# Modbus.net
KiCad netlist of a schematic drawn in Altium Designer
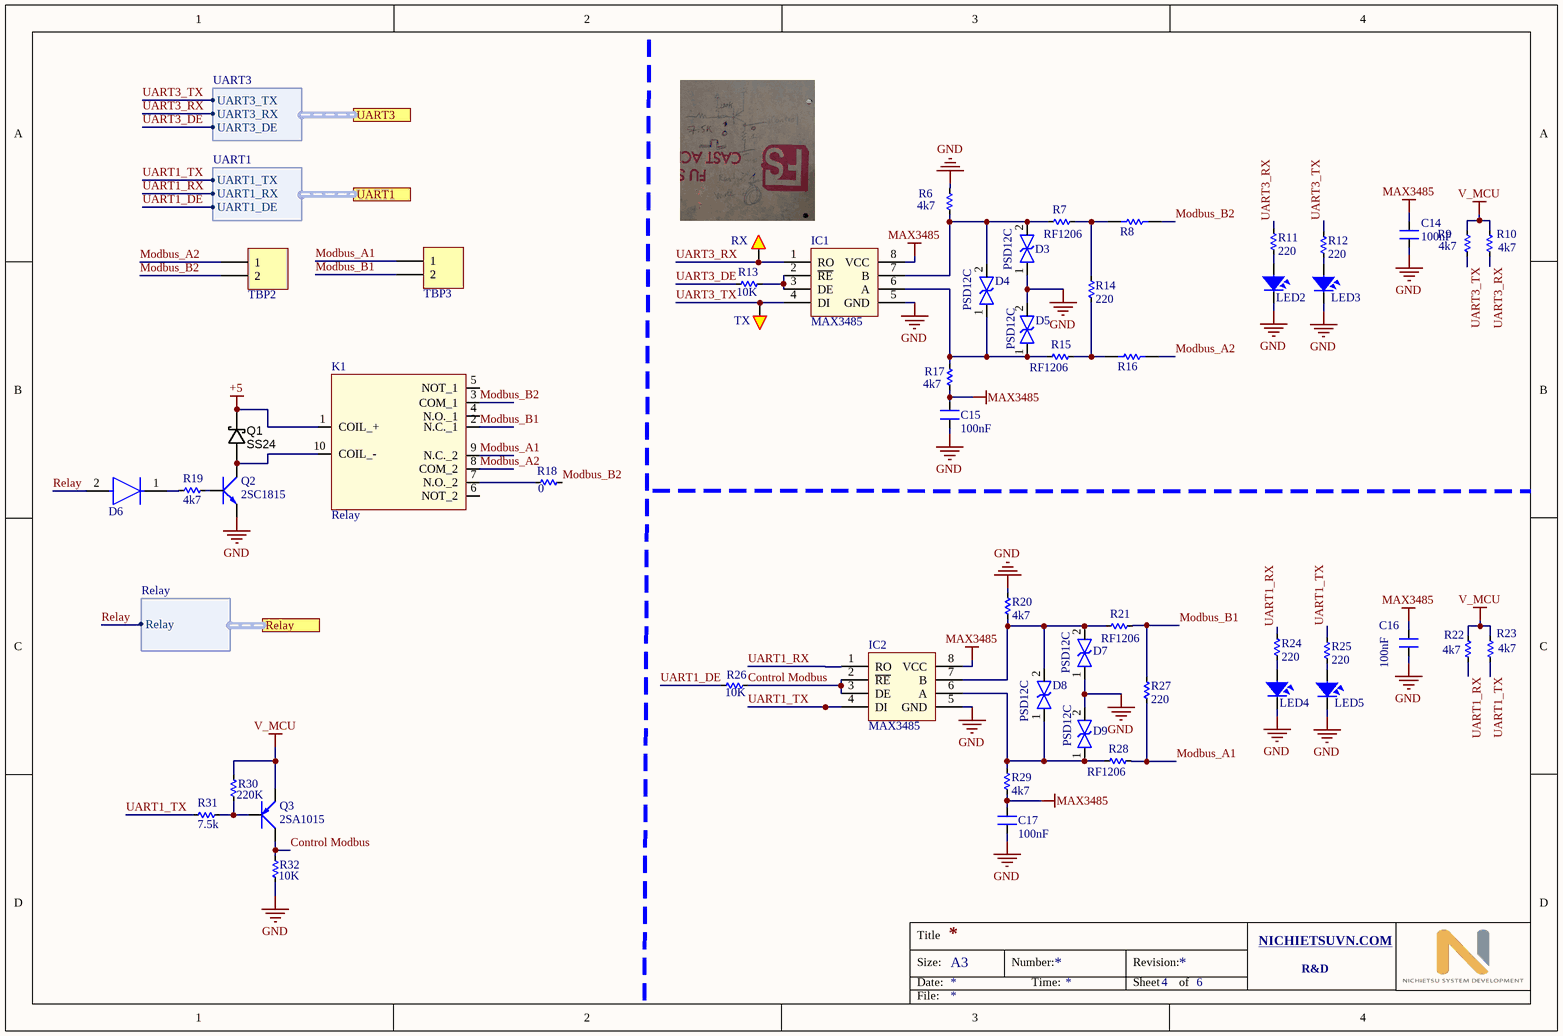
[diagram p0: Modbus.SchDoc]

(export (version "E")
  (design (tool "Eeschema 10.0.6"))
  (components
    (comp (ref "B1")
      (value "RX")
      (footprint "SMD_1.5")
      (description "WR-PHD 2.54 mm Angled Socket Header")
      (fields
        (field (name "MANUFACTURER") "Würth Elektronik eiSos GmbH")
        (field (name "PARTNO") "613002143121")
        (field (name "CREATED BY") "Karrer Zheng")
      )
      (libsource (lib "Nichietsuvn") (part "Test"))
    )
    (comp (ref "B2")
      (value "TX")
      (footprint "SMD_1.5")
      (description "WR-PHD 2.54 mm Angled Socket Header")
      (fields
        (field (name "MANUFACTURER") "Würth Elektronik eiSos GmbH")
        (field (name "PARTNO") "613002143121")
        (field (name "CREATED BY") "Karrer Zheng")
      )
      (libsource (lib "Nichietsuvn") (part "Test"))
    )
    (comp (ref "C14") (value "100nF") (footprint "CN-SMD-0603") (libsource (lib "thu vien 3d") (part "CN")))
    (comp (ref "C15") (value "100nF") (footprint "CN-SMD-0603") (libsource (lib "thu vien 3d") (part "CN")))
    (comp (ref "C16") (value "100nF") (footprint "CN-SMD-0603") (libsource (lib "thu vien 3d") (part "CN")))
    (comp (ref "C17") (value "100nF") (footprint "CN-SMD-0603") (libsource (lib "thu vien 3d") (part "CN")))
    (comp (ref "D3")
      (value "PSD12C")
      (footprint "PSD12C")
      (description "diode tvs")
      (libsource (lib "Nichietsuvn") (part "PSD12C"))
    )
    (comp (ref "D4")
      (value "PSD12C")
      (footprint "PSD12C")
      (description "diode tvs")
      (libsource (lib "Nichietsuvn") (part "PSD12C"))
    )
    (comp (ref "D5")
      (value "PSD12C")
      (footprint "PSD12C")
      (description "diode tvs")
      (libsource (lib "Nichietsuvn") (part "PSD12C"))
    )
    (comp (ref "D6")
      (value "1N4148W-HE3-08")
      (footprint "1N4148")
      (libsource (lib "All Library") (part "1N4148W-HE3-08"))
    )
    (comp (ref "D7")
      (value "PSD12C")
      (footprint "PSD12C")
      (description "diode tvs")
      (libsource (lib "Nichietsuvn") (part "PSD12C"))
    )
    (comp (ref "D8")
      (value "PSD12C")
      (footprint "PSD12C")
      (description "diode tvs")
      (libsource (lib "Nichietsuvn") (part "PSD12C"))
    )
    (comp (ref "D9")
      (value "PSD12C")
      (footprint "PSD12C")
      (description "diode tvs")
      (libsource (lib "Nichietsuvn") (part "PSD12C"))
    )
    (comp (ref "IC1")
      (value "MAX3485")
      (footprint "SO8")
      (description "RS232 - RS485 (Same sn75176)")
      (libsource (lib "thu vien 3d") (part "MAX485"))
    )
    (comp (ref "IC2")
      (value "MAX3485")
      (footprint "SO8")
      (description "RS232 - RS485 (Same sn75176)")
      (libsource (lib "thu vien 3d") (part "MAX485"))
    )
    (comp (ref "K1")
      (value "Relay")
      (footprint "Relay EA2")
      (description "Relay or Contactor")
      (fields (field (name "MANUFACTURER_PART_NUMBER") "EA2-5NU"))
      (libsource (lib "All Library") (part "EA2-5NU"))
    )
    (comp (ref "LED2")
      (value "LED")
      (footprint "LED-0805-Blue")
      (libsource (lib "thu vien 3d") (part "LED SMD"))
    )
    (comp (ref "LED3")
      (value "LED")
      (footprint "LED-0805-Blue")
      (libsource (lib "thu vien 3d") (part "LED SMD"))
    )
    (comp (ref "LED4")
      (value "LED")
      (footprint "LED-0805-Blue")
      (libsource (lib "thu vien 3d") (part "LED SMD"))
    )
    (comp (ref "LED5")
      (value "LED")
      (footprint "LED-0805-Blue")
      (libsource (lib "thu vien 3d") (part "LED SMD"))
    )
    (comp (ref "Q1")
      (value "SS24")
      (footprint "DO-214AC")
      (description "Diode Schottky 40V 2A Surface Mount DO-214AC (SMA)")
      (libsource (lib "All Library") (part "DIODE_SS24"))
    )
    (comp (ref "Q2")
      (value "2SC1815")
      (footprint "SOT23-321")
      (description "NPN 600mW, ECB")
      (libsource (lib "thu vien 3d") (part "2SC1815"))
    )
    (comp (ref "Q3")
      (value "2SA1015")
      (footprint "SOT23-321")
      (description "PNP 600mW, ECB")
      (libsource (lib "thu vien 3d") (part "2SA1015"))
    )
    (comp (ref "R6")
      (value "4k7")
      (footprint "RES-SMD-0603")
      (description "Resistor")
      (fields
        (field (name "MANUFACTURER") "Generic Components")
        (field (name "PUBLISHER") "Altium Hobart Technology Centre")
      )
      (libsource (lib "thu vien 3d") (part "Res-SMD"))
    )
    (comp (ref "R7")
      (value "RF1206")
      (footprint "RES-SMD-1206")
      (description "Resistor")
      (fields
        (field (name "MANUFACTURER") "Generic Components")
        (field (name "PUBLISHER") "Altium Hobart Technology Centre")
      )
      (libsource (lib "thu vien 3d") (part "Res-SMD"))
    )
    (comp (ref "R8")
      (value "0R/R0603")
      (footprint "R0603")
      (description "RES SMD 0.0OHM JUMPER 1/10W 0603")
      (fields
        (field (name "MANUFACTURER") "Yageo")
        (field (name "MANUFACTURER PART NUMBER") "RC0603JR-070RL")
      )
      (libsource (lib "All Library") (part "RES_0R_R0603"))
    )
    (comp (ref "R9")
      (value "4k7")
      (footprint "RES-SMD-0603")
      (description "Resistor")
      (fields
        (field (name "MANUFACTURER") "Generic Components")
        (field (name "PUBLISHER") "Altium Hobart Technology Centre")
      )
      (libsource (lib "thu vien 3d") (part "Res-SMD"))
    )
    (comp (ref "R10")
      (value "4k7")
      (footprint "RES-SMD-0603")
      (description "Resistor")
      (fields
        (field (name "MANUFACTURER") "Generic Components")
        (field (name "PUBLISHER") "Altium Hobart Technology Centre")
      )
      (libsource (lib "thu vien 3d") (part "Res-SMD"))
    )
    (comp (ref "R11")
      (value "220")
      (footprint "RES-SMD-0603")
      (description "Resistor")
      (fields
        (field (name "MANUFACTURER") "Generic Components")
        (field (name "PUBLISHER") "Altium Hobart Technology Centre")
      )
      (libsource (lib "thu vien 3d") (part "Res-SMD"))
    )
    (comp (ref "R12")
      (value "220")
      (footprint "RES-SMD-0603")
      (description "Resistor")
      (fields
        (field (name "MANUFACTURER") "Generic Components")
        (field (name "PUBLISHER") "Altium Hobart Technology Centre")
      )
      (libsource (lib "thu vien 3d") (part "Res-SMD"))
    )
    (comp (ref "R13")
      (value "10K")
      (footprint "RES-SMD-0603")
      (description "Resistor")
      (fields
        (field (name "MANUFACTURER") "Generic Components")
        (field (name "PUBLISHER") "Altium Hobart Technology Centre")
      )
      (libsource (lib "thu vien 3d") (part "Res-SMD"))
    )
    (comp (ref "R14")
      (value "220")
      (footprint "RES-SMD-0603")
      (description "Resistor")
      (fields
        (field (name "MANUFACTURER") "Generic Components")
        (field (name "PUBLISHER") "Altium Hobart Technology Centre")
      )
      (libsource (lib "thu vien 3d") (part "Res-SMD"))
    )
    (comp (ref "R15")
      (value "RF1206")
      (footprint "RES-SMD-1206")
      (description "Resistor")
      (fields
        (field (name "MANUFACTURER") "Generic Components")
        (field (name "PUBLISHER") "Altium Hobart Technology Centre")
      )
      (libsource (lib "thu vien 3d") (part "Res-SMD"))
    )
    (comp (ref "R16")
      (value "0R/R0603")
      (footprint "R0603")
      (description "RES SMD 0.0OHM JUMPER 1/10W 0603")
      (fields
        (field (name "MANUFACTURER") "Yageo")
        (field (name "MANUFACTURER PART NUMBER") "RC0603JR-070RL")
      )
      (libsource (lib "All Library") (part "RES_0R_R0603"))
    )
    (comp (ref "R17")
      (value "4k7")
      (footprint "RES-SMD-0603")
      (description "Resistor")
      (fields
        (field (name "MANUFACTURER") "Generic Components")
        (field (name "PUBLISHER") "Altium Hobart Technology Centre")
      )
      (libsource (lib "thu vien 3d") (part "Res-SMD"))
    )
    (comp (ref "R18")
      (value "0")
      (footprint "RES-SMD-0603")
      (description "Resistor")
      (fields
        (field (name "MANUFACTURER") "Generic Components")
        (field (name "PUBLISHER") "Altium Hobart Technology Centre")
      )
      (libsource (lib "thu vien 3d") (part "Res-SMD"))
    )
    (comp (ref "R19")
      (value "4k7")
      (footprint "RES-SMD-0603")
      (description "Resistor")
      (fields
        (field (name "MANUFACTURER") "Generic Components")
        (field (name "PUBLISHER") "Altium Hobart Technology Centre")
      )
      (libsource (lib "thu vien 3d") (part "Res-SMD"))
    )
    (comp (ref "R20")
      (value "4k7")
      (footprint "RES-SMD-0603")
      (description "Resistor")
      (fields
        (field (name "MANUFACTURER") "Generic Components")
        (field (name "PUBLISHER") "Altium Hobart Technology Centre")
      )
      (libsource (lib "thu vien 3d") (part "Res-SMD"))
    )
    (comp (ref "R21")
      (value "RF1206")
      (footprint "RES-SMD-1206")
      (description "Resistor")
      (fields
        (field (name "MANUFACTURER") "Generic Components")
        (field (name "PUBLISHER") "Altium Hobart Technology Centre")
      )
      (libsource (lib "thu vien 3d") (part "Res-SMD"))
    )
    (comp (ref "R22")
      (value "4k7")
      (footprint "RES-SMD-0603")
      (description "Resistor")
      (fields
        (field (name "MANUFACTURER") "Generic Components")
        (field (name "PUBLISHER") "Altium Hobart Technology Centre")
      )
      (libsource (lib "thu vien 3d") (part "Res-SMD"))
    )
    (comp (ref "R23")
      (value "4k7")
      (footprint "RES-SMD-0603")
      (description "Resistor")
      (fields
        (field (name "MANUFACTURER") "Generic Components")
        (field (name "PUBLISHER") "Altium Hobart Technology Centre")
      )
      (libsource (lib "thu vien 3d") (part "Res-SMD"))
    )
    (comp (ref "R24")
      (value "220")
      (footprint "RES-SMD-0603")
      (description "Resistor")
      (fields
        (field (name "MANUFACTURER") "Generic Components")
        (field (name "PUBLISHER") "Altium Hobart Technology Centre")
      )
      (libsource (lib "thu vien 3d") (part "Res-SMD"))
    )
    (comp (ref "R25")
      (value "220")
      (footprint "RES-SMD-0603")
      (description "Resistor")
      (fields
        (field (name "MANUFACTURER") "Generic Components")
        (field (name "PUBLISHER") "Altium Hobart Technology Centre")
      )
      (libsource (lib "thu vien 3d") (part "Res-SMD"))
    )
    (comp (ref "R26")
      (value "10K")
      (footprint "RES-SMD-0603")
      (description "Resistor")
      (fields
        (field (name "MANUFACTURER") "Generic Components")
        (field (name "PUBLISHER") "Altium Hobart Technology Centre")
      )
      (libsource (lib "thu vien 3d") (part "Res-SMD"))
    )
    (comp (ref "R27")
      (value "220")
      (footprint "RES-SMD-0603")
      (description "Resistor")
      (fields
        (field (name "MANUFACTURER") "Generic Components")
        (field (name "PUBLISHER") "Altium Hobart Technology Centre")
      )
      (libsource (lib "thu vien 3d") (part "Res-SMD"))
    )
    (comp (ref "R28")
      (value "RF1206")
      (footprint "RES-SMD-1206")
      (description "Resistor")
      (fields
        (field (name "MANUFACTURER") "Generic Components")
        (field (name "PUBLISHER") "Altium Hobart Technology Centre")
      )
      (libsource (lib "thu vien 3d") (part "Res-SMD"))
    )
    (comp (ref "R29")
      (value "4k7")
      (footprint "RES-SMD-0603")
      (description "Resistor")
      (fields
        (field (name "MANUFACTURER") "Generic Components")
        (field (name "PUBLISHER") "Altium Hobart Technology Centre")
      )
      (libsource (lib "thu vien 3d") (part "Res-SMD"))
    )
    (comp (ref "R30")
      (value "220K")
      (footprint "RES-SMD-0603")
      (description "Resistor")
      (fields
        (field (name "MANUFACTURER") "Generic Components")
        (field (name "PUBLISHER") "Altium Hobart Technology Centre")
      )
      (libsource (lib "thu vien 3d") (part "Res-SMD"))
    )
    (comp (ref "R31")
      (value "7.5k")
      (footprint "RES-SMD-0603")
      (description "Resistor")
      (fields
        (field (name "MANUFACTURER") "Generic Components")
        (field (name "PUBLISHER") "Altium Hobart Technology Centre")
      )
      (libsource (lib "thu vien 3d") (part "Res-SMD"))
    )
    (comp (ref "R32")
      (value "10K")
      (footprint "RES-SMD-0603")
      (description "Resistor")
      (fields
        (field (name "MANUFACTURER") "Generic Components")
        (field (name "PUBLISHER") "Altium Hobart Technology Centre")
      )
      (libsource (lib "thu vien 3d") (part "Res-SMD"))
    )
    (comp (ref "TBP2")
      (value "WE-Terminal Blocks Plugable Type 691322310002")
      (footprint "Terminal_Blocks_Pluggable_Socket__Right_Angle__3.81_mm_Pitch__2_Position")
      (description "WR-TBL Terminal block - serie 322 - 3.81 mm")
      (libsource (lib "All Library") (part "Terminal_Blocks_Pluggable_Socket__Right_Angle__3.81_mm_Pitch__2_Position"))
    )
    (comp (ref "TBP3")
      (value "WE-Terminal Blocks Plugable Type 691322310002")
      (footprint "Terminal_Blocks_Pluggable_Socket__Right_Angle__3.81_mm_Pitch__2_Position")
      (description "WR-TBL Terminal block - serie 322 - 3.81 mm")
      (libsource (lib "All Library") (part "Terminal_Blocks_Pluggable_Socket__Right_Angle__3.81_mm_Pitch__2_Position"))
    )
  )
  (nets
    (net (code "3") (name "+5") (class "Default")
      (node (ref "K1") (pin "1") (pinfunction "COIL_+_1") (pintype "passive"))
      (node (ref "Q1") (pin "C") (pinfunction "C_C") (pintype "passive"))
    )
    (net (code "4") (name "/Control Modbus") (class "Default")
      (node (ref "IC2") (pin "2") (pinfunction "~{RE}_2") (pintype "passive"))
      (node (ref "IC2") (pin "3") (pinfunction "DE_3") (pintype "passive"))
      (node (ref "Q3") (pin "2") (pinfunction "C_2") (pintype "passive"))
      (node (ref "R26") (pin "2") (pinfunction "2_2") (pintype "passive"))
      (node (ref "R32") (pin "2") (pinfunction "2_2") (pintype "passive"))
    )
    (net (code "5") (name "/Modbus_A1") (class "Default")
      (node (ref "K1") (pin "9") (pinfunction "N.C._2_9") (pintype "passive"))
      (node (ref "R27") (pin "2") (pinfunction "2_2") (pintype "passive"))
      (node (ref "R28") (pin "1") (pinfunction "1_1") (pintype "passive"))
      (node (ref "TBP3") (pin "1") (pinfunction "1_1") (pintype "passive"))
    )
    (net (code "6") (name "/Modbus_A2") (class "Default")
      (node (ref "K1") (pin "8") (pinfunction "COM_2_8") (pintype "passive"))
      (node (ref "R16") (pin "2") (pinfunction "2_2") (pintype "passive"))
      (node (ref "TBP2") (pin "1") (pinfunction "1_1") (pintype "passive"))
    )
    (net (code "7") (name "/Modbus_B1") (class "Default")
      (node (ref "K1") (pin "2") (pinfunction "N.C._1_2") (pintype "passive"))
      (node (ref "R21") (pin "1") (pinfunction "1_1") (pintype "passive"))
      (node (ref "R27") (pin "1") (pinfunction "1_1") (pintype "passive"))
      (node (ref "TBP3") (pin "2") (pinfunction "2_2") (pintype "passive"))
    )
    (net (code "8") (name "/Modbus_B2") (class "Default")
      (node (ref "K1") (pin "3") (pinfunction "COM_1_3") (pintype "passive"))
      (node (ref "R18") (pin "2") (pinfunction "2_2") (pintype "passive"))
      (node (ref "R8") (pin "2") (pinfunction "2_2") (pintype "passive"))
      (node (ref "TBP2") (pin "2") (pinfunction "2_2") (pintype "passive"))
    )
    (net (code "9") (name "/Relay") (class "Default")
      (node (ref "D6") (pin "2") (pinfunction "A_2") (pintype "passive"))
    )
    (net (code "10") (name "/UART1_DE") (class "Default")
      (node (ref "R26") (pin "1") (pinfunction "1_1") (pintype "passive"))
    )
    (net (code "11") (name "/UART1_RX") (class "Default")
      (node (ref "IC2") (pin "1") (pinfunction "RO_1") (pintype "passive"))
      (node (ref "R22") (pin "2") (pinfunction "2_2") (pintype "passive"))
      (node (ref "R24") (pin "1") (pinfunction "1_1") (pintype "passive"))
    )
    (net (code "12") (name "/UART1_TX") (class "Default")
      (node (ref "IC2") (pin "4") (pinfunction "DI_4") (pintype "passive"))
      (node (ref "R23") (pin "2") (pinfunction "2_2") (pintype "passive"))
      (node (ref "R25") (pin "1") (pinfunction "1_1") (pintype "passive"))
      (node (ref "R31") (pin "1") (pinfunction "1_1") (pintype "passive"))
    )
    (net (code "13") (name "/UART3_DE") (class "Default")
      (node (ref "R13") (pin "1") (pinfunction "1_1") (pintype "passive"))
    )
    (net (code "14") (name "/UART3_RX") (class "Default")
      (node (ref "B1") (pin "1") (pinfunction "1_1") (pintype "passive"))
      (node (ref "IC1") (pin "1") (pinfunction "RO_1") (pintype "passive"))
      (node (ref "R10") (pin "2") (pinfunction "2_2") (pintype "passive"))
      (node (ref "R11") (pin "1") (pinfunction "1_1") (pintype "passive"))
    )
    (net (code "15") (name "/UART3_TX") (class "Default")
      (node (ref "B2") (pin "1") (pinfunction "1_1") (pintype "passive"))
      (node (ref "IC1") (pin "4") (pinfunction "DI_4") (pintype "passive"))
      (node (ref "R12") (pin "1") (pinfunction "1_1") (pintype "passive"))
      (node (ref "R9") (pin "2") (pinfunction "2_2") (pintype "passive"))
    )
    (net (code "19") (name "GND") (class "Default")
      (node (ref "C14") (pin "1") (pinfunction "1_1") (pintype "passive"))
      (node (ref "C15") (pin "2") (pinfunction "2_2") (pintype "passive"))
      (node (ref "C16") (pin "1") (pinfunction "1_1") (pintype "passive"))
      (node (ref "C17") (pin "2") (pinfunction "2_2") (pintype "passive"))
      (node (ref "D3") (pin "1") (pinfunction "1_1") (pintype "passive"))
      (node (ref "D5") (pin "2") (pinfunction "2_2") (pintype "passive"))
      (node (ref "D7") (pin "1") (pinfunction "1_1") (pintype "passive"))
      (node (ref "D9") (pin "2") (pinfunction "2_2") (pintype "passive"))
      (node (ref "IC1") (pin "5") (pinfunction "GND_5") (pintype "passive"))
      (node (ref "IC2") (pin "5") (pinfunction "GND_5") (pintype "passive"))
      (node (ref "LED2") (pin "2") (pinfunction "2_2") (pintype "passive"))
      (node (ref "LED3") (pin "2") (pinfunction "2_2") (pintype "passive"))
      (node (ref "LED4") (pin "2") (pinfunction "2_2") (pintype "passive"))
      (node (ref "LED5") (pin "2") (pinfunction "2_2") (pintype "passive"))
      (node (ref "Q2") (pin "1") (pinfunction "E_1") (pintype "passive"))
      (node (ref "R20") (pin "1") (pinfunction "1_1") (pintype "passive"))
      (node (ref "R32") (pin "1") (pinfunction "1_1") (pintype "passive"))
      (node (ref "R6") (pin "1") (pinfunction "1_1") (pintype "passive"))
    )
    (net (code "20") (name "MAX3485") (class "Default")
      (node (ref "C14") (pin "2") (pinfunction "2_2") (pintype "passive"))
      (node (ref "C15") (pin "1") (pinfunction "1_1") (pintype "passive"))
      (node (ref "C16") (pin "2") (pinfunction "2_2") (pintype "passive"))
      (node (ref "C17") (pin "1") (pinfunction "1_1") (pintype "passive"))
      (node (ref "IC1") (pin "8") (pinfunction "VCC_8") (pintype "passive"))
      (node (ref "IC2") (pin "8") (pinfunction "VCC_8") (pintype "passive"))
      (node (ref "R17") (pin "1") (pinfunction "1_1") (pintype "passive"))
      (node (ref "R29") (pin "1") (pinfunction "1_1") (pintype "passive"))
    )
    (net (code "21") (name "Net-(D6-C)") (class "Default")
      (node (ref "D6") (pin "1") (pinfunction "C_1") (pintype "passive"))
      (node (ref "R19") (pin "2") (pinfunction "2_2") (pintype "passive"))
    )
    (net (code "22") (name "Net-(IC1-A)") (class "Default")
      (node (ref "D4") (pin "1") (pinfunction "1_1") (pintype "passive"))
      (node (ref "D5") (pin "1") (pinfunction "1_1") (pintype "passive"))
      (node (ref "IC1") (pin "6") (pinfunction "A_6") (pintype "passive"))
      (node (ref "R15") (pin "2") (pinfunction "2_2") (pintype "passive"))
      (node (ref "R17") (pin "2") (pinfunction "2_2") (pintype "passive"))
    )
    (net (code "23") (name "Net-(IC1-B)") (class "Default")
      (node (ref "D3") (pin "2") (pinfunction "2_2") (pintype "passive"))
      (node (ref "D4") (pin "2") (pinfunction "2_2") (pintype "passive"))
      (node (ref "IC1") (pin "7") (pinfunction "B_7") (pintype "passive"))
      (node (ref "R6") (pin "2") (pinfunction "2_2") (pintype "passive"))
      (node (ref "R7") (pin "2") (pinfunction "2_2") (pintype "passive"))
    )
    (net (code "24") (name "Net-(IC1-DE)") (class "Default")
      (node (ref "IC1") (pin "2") (pinfunction "~{RE}_2") (pintype "passive"))
      (node (ref "IC1") (pin "3") (pinfunction "DE_3") (pintype "passive"))
      (node (ref "R13") (pin "2") (pinfunction "2_2") (pintype "passive"))
    )
    (net (code "25") (name "Net-(IC2-A)") (class "Default")
      (node (ref "D8") (pin "1") (pinfunction "1_1") (pintype "passive"))
      (node (ref "D9") (pin "1") (pinfunction "1_1") (pintype "passive"))
      (node (ref "IC2") (pin "6") (pinfunction "A_6") (pintype "passive"))
      (node (ref "R28") (pin "2") (pinfunction "2_2") (pintype "passive"))
      (node (ref "R29") (pin "2") (pinfunction "2_2") (pintype "passive"))
    )
    (net (code "26") (name "Net-(IC2-B)") (class "Default")
      (node (ref "D7") (pin "2") (pinfunction "2_2") (pintype "passive"))
      (node (ref "D8") (pin "2") (pinfunction "2_2") (pintype "passive"))
      (node (ref "IC2") (pin "7") (pinfunction "B_7") (pintype "passive"))
      (node (ref "R20") (pin "2") (pinfunction "2_2") (pintype "passive"))
      (node (ref "R21") (pin "2") (pinfunction "2_2") (pintype "passive"))
    )
    (net (code "27") (name "Net-(K1-COIL_-)") (class "Default")
      (node (ref "K1") (pin "10") (pinfunction "COIL_-_10") (pintype "passive"))
      (node (ref "Q1") (pin "A") (pinfunction "A_A") (pintype "passive"))
      (node (ref "Q2") (pin "2") (pinfunction "C_2") (pintype "passive"))
    )
    (net (code "28") (name "Net-(K1-N.O._2)") (class "Default")
      (node (ref "K1") (pin "7") (pinfunction "N.O._2_7") (pintype "passive"))
      (node (ref "R18") (pin "1") (pinfunction "1_1") (pintype "passive"))
    )
    (net (code "29") (name "Net-(LED2-Pad1)") (class "Default")
      (node (ref "LED2") (pin "1") (pinfunction "1_1") (pintype "passive"))
      (node (ref "R11") (pin "2") (pinfunction "2_2") (pintype "passive"))
    )
    (net (code "30") (name "Net-(LED3-Pad1)") (class "Default")
      (node (ref "LED3") (pin "1") (pinfunction "1_1") (pintype "passive"))
      (node (ref "R12") (pin "2") (pinfunction "2_2") (pintype "passive"))
    )
    (net (code "31") (name "Net-(LED4-Pad1)") (class "Default")
      (node (ref "LED4") (pin "1") (pinfunction "1_1") (pintype "passive"))
      (node (ref "R24") (pin "2") (pinfunction "2_2") (pintype "passive"))
    )
    (net (code "32") (name "Net-(LED5-Pad1)") (class "Default")
      (node (ref "LED5") (pin "1") (pinfunction "1_1") (pintype "passive"))
      (node (ref "R25") (pin "2") (pinfunction "2_2") (pintype "passive"))
    )
    (net (code "33") (name "Net-(Q2-B)") (class "Default")
      (node (ref "Q2") (pin "3") (pinfunction "B_3") (pintype "passive"))
      (node (ref "R19") (pin "1") (pinfunction "1_1") (pintype "passive"))
    )
    (net (code "34") (name "Net-(Q3-B)") (class "Default")
      (node (ref "Q3") (pin "3") (pinfunction "B_3") (pintype "passive"))
      (node (ref "R30") (pin "1") (pinfunction "1_1") (pintype "passive"))
      (node (ref "R31") (pin "2") (pinfunction "2_2") (pintype "passive"))
    )
    (net (code "35") (name "Net-(R14-Pad1)") (class "Default")
      (node (ref "R14") (pin "1") (pinfunction "1_1") (pintype "passive"))
      (node (ref "R7") (pin "1") (pinfunction "1_1") (pintype "passive"))
      (node (ref "R8") (pin "1") (pinfunction "1_1") (pintype "passive"))
    )
    (net (code "36") (name "Net-(R14-Pad2)") (class "Default")
      (node (ref "R14") (pin "2") (pinfunction "2_2") (pintype "passive"))
      (node (ref "R15") (pin "1") (pinfunction "1_1") (pintype "passive"))
      (node (ref "R16") (pin "1") (pinfunction "1_1") (pintype "passive"))
    )
    (net (code "37") (name "V_MCU") (class "Default")
      (node (ref "Q3") (pin "1") (pinfunction "E_1") (pintype "passive"))
      (node (ref "R10") (pin "1") (pinfunction "1_1") (pintype "passive"))
      (node (ref "R22") (pin "1") (pinfunction "1_1") (pintype "passive"))
      (node (ref "R23") (pin "1") (pinfunction "1_1") (pintype "passive"))
      (node (ref "R30") (pin "2") (pinfunction "2_2") (pintype "passive"))
      (node (ref "R9") (pin "1") (pinfunction "1_1") (pintype "passive"))
    )
    (net (code "38") (name "unconnected-(K1-N.O._1-Pad4)") (class "Default")
      (node (ref "K1") (pin "4") (pinfunction "N.O._1_4") (pintype "passive"))
    )
    (net (code "39") (name "unconnected-(K1-NOT_1-Pad5)") (class "Default")
      (node (ref "K1") (pin "5") (pinfunction "NOT_1_5") (pintype "passive"))
    )
    (net (code "40") (name "unconnected-(K1-NOT_2-Pad6)") (class "Default")
      (node (ref "K1") (pin "6") (pinfunction "NOT_2_6") (pintype "passive"))
    )
  )
)
